# Motherboard.net
KiCad netlist of a schematic drawn in EAGLE
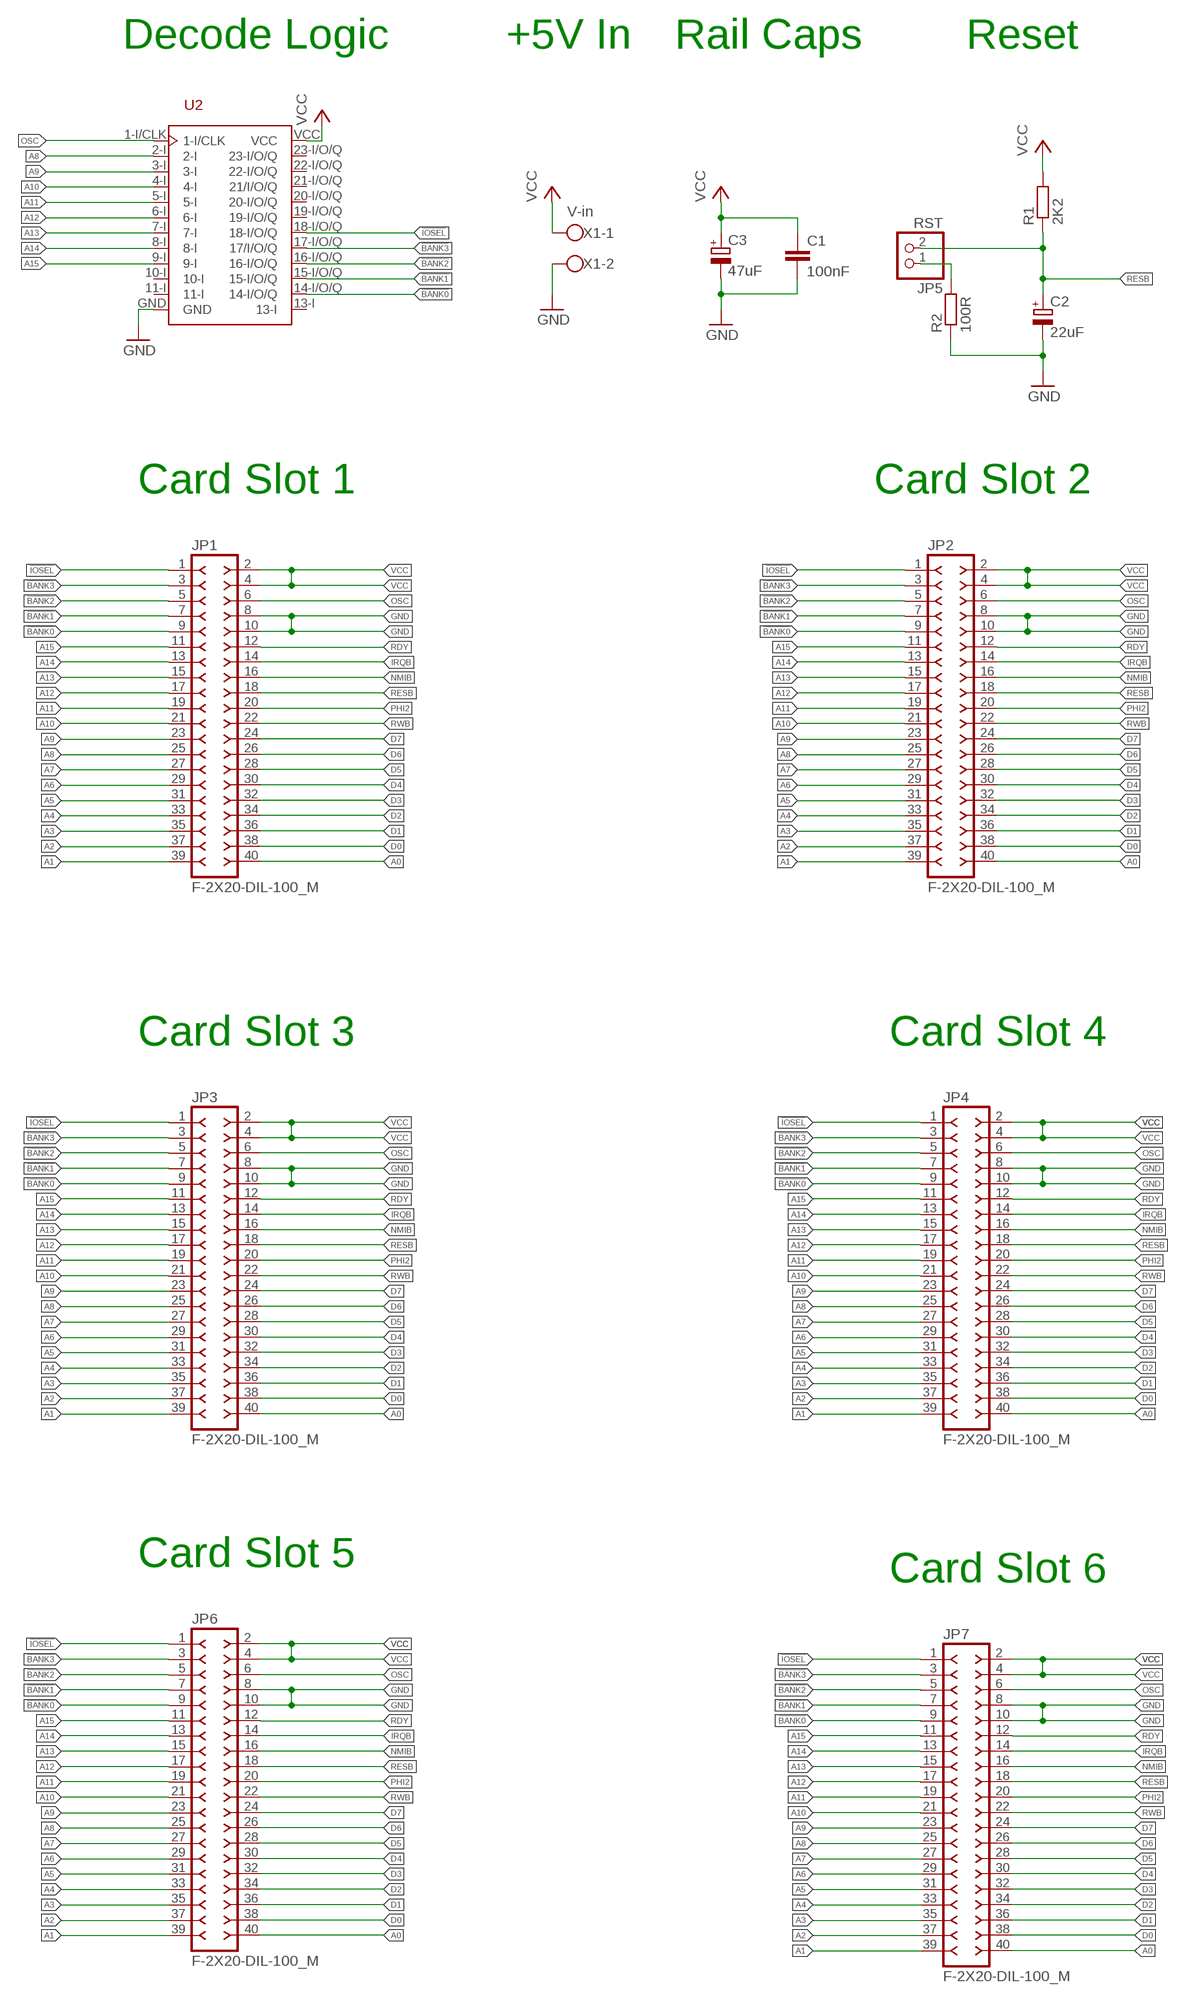
[diagram p0: schematic, sheet 1]

(export (version "E")
  (design (tool "Eeschema 10.0.6"))
  (components
    (comp (ref "C1")
      (value "100nF")
      (footprint "eagle-import:C050-025X075")
      (libsource (lib "eagle-import") (part "C-EU050-025X075"))
    )
    (comp (ref "C2")
      (value "22uF")
      (footprint "eagle-import:E2-5")
      (libsource (lib "eagle-import") (part "CPOL-EUE2-5"))
    )
    (comp (ref "C3")
      (value "47uF")
      (footprint "eagle-import:E2,5-7")
      (libsource (lib "eagle-import") (part "CPOL-EUE2.5-7"))
    )
    (comp (ref "JP1")
      (value "F-2X20-DIL-100_M")
      (footprint "eagle-import:DIL-100-2X20_M")
      (libsource (lib "eagle-import") (part "F-2X20-DIL-100_M"))
    )
    (comp (ref "JP2")
      (value "F-2X20-DIL-100_M")
      (footprint "eagle-import:DIL-100-2X20_M")
      (libsource (lib "eagle-import") (part "F-2X20-DIL-100_M"))
    )
    (comp (ref "JP3")
      (value "F-2X20-DIL-100_M")
      (footprint "eagle-import:DIL-100-2X20_M")
      (libsource (lib "eagle-import") (part "F-2X20-DIL-100_M"))
    )
    (comp (ref "JP4")
      (value "F-2X20-DIL-100_M")
      (footprint "eagle-import:DIL-100-2X20_M")
      (libsource (lib "eagle-import") (part "F-2X20-DIL-100_M"))
    )
    (comp (ref "JP5")
      (value "RST")
      (footprint "eagle-import:1X02")
      (libsource (lib "eagle-import") (part "PINHD-1X2"))
    )
    (comp (ref "JP6")
      (value "F-2X20-DIL-100_M")
      (footprint "eagle-import:DIL-100-2X20_M")
      (libsource (lib "eagle-import") (part "F-2X20-DIL-100_M"))
    )
    (comp (ref "JP7")
      (value "F-2X20-DIL-100_M")
      (footprint "eagle-import:DIL-100-2X20_M")
      (libsource (lib "eagle-import") (part "F-2X20-DIL-100_M"))
    )
    (comp (ref "R1")
      (value "2K2")
      (footprint "eagle-import:0207_10")
      (libsource (lib "eagle-import") (part "R-EU_0207/10"))
    )
    (comp (ref "R2")
      (value "100R")
      (footprint "eagle-import:0207_10")
      (libsource (lib "eagle-import") (part "R-EU_0207/10"))
    )
    (comp (ref "U2")
      (value "GAL22V10D-DIP")
      (footprint "eagle-import:DIP24")
      (libsource (lib "eagle-import") (part "GAL22V10D-DIP"))
    )
    (comp (ref "X1")
      (value "V-in")
      (footprint "eagle-import:W237-102")
      (fields (field (name "MPN") "237-102"))
      (libsource (lib "eagle-import") (part "W237-102"))
    )
  )
  (nets
    (net (code "1") (name "/~{BANK0}") (class "Default")
      (node (ref "JP1") (pin "9") (pinfunction "9_9") (pintype "passive"))
      (node (ref "JP2") (pin "9") (pinfunction "9_9") (pintype "passive"))
      (node (ref "JP3") (pin "9") (pinfunction "9_9") (pintype "passive"))
      (node (ref "JP4") (pin "9") (pinfunction "9_9") (pintype "passive"))
      (node (ref "JP6") (pin "9") (pinfunction "9_9") (pintype "passive"))
      (node (ref "JP7") (pin "9") (pinfunction "9_9") (pintype "passive"))
      (node (ref "U2") (pin "14-I/O/Q") (pinfunction "14-I/O/Q_14-I/O/Q") (pintype "bidirectional"))
    )
    (net (code "2") (name "/~{BANK1}") (class "Default")
      (node (ref "JP1") (pin "7") (pinfunction "7_7") (pintype "passive"))
      (node (ref "JP2") (pin "7") (pinfunction "7_7") (pintype "passive"))
      (node (ref "JP3") (pin "7") (pinfunction "7_7") (pintype "passive"))
      (node (ref "JP4") (pin "7") (pinfunction "7_7") (pintype "passive"))
      (node (ref "JP6") (pin "7") (pinfunction "7_7") (pintype "passive"))
      (node (ref "JP7") (pin "7") (pinfunction "7_7") (pintype "passive"))
      (node (ref "U2") (pin "15-I/O/Q") (pinfunction "15-I/O/Q_15-I/O/Q") (pintype "bidirectional"))
    )
    (net (code "3") (name "/~{BANK2}") (class "Default")
      (node (ref "JP1") (pin "5") (pinfunction "5_5") (pintype "passive"))
      (node (ref "JP2") (pin "5") (pinfunction "5_5") (pintype "passive"))
      (node (ref "JP3") (pin "5") (pinfunction "5_5") (pintype "passive"))
      (node (ref "JP4") (pin "5") (pinfunction "5_5") (pintype "passive"))
      (node (ref "JP6") (pin "5") (pinfunction "5_5") (pintype "passive"))
      (node (ref "JP7") (pin "5") (pinfunction "5_5") (pintype "passive"))
      (node (ref "U2") (pin "16-I/O/Q") (pinfunction "16-I/O/Q_16-I/O/Q") (pintype "bidirectional"))
    )
    (net (code "4") (name "/~{BANK3}") (class "Default")
      (node (ref "JP1") (pin "3") (pinfunction "3_3") (pintype "passive"))
      (node (ref "JP2") (pin "3") (pinfunction "3_3") (pintype "passive"))
      (node (ref "JP3") (pin "3") (pinfunction "3_3") (pintype "passive"))
      (node (ref "JP4") (pin "3") (pinfunction "3_3") (pintype "passive"))
      (node (ref "JP6") (pin "3") (pinfunction "3_3") (pintype "passive"))
      (node (ref "JP7") (pin "3") (pinfunction "3_3") (pintype "passive"))
      (node (ref "U2") (pin "17-I/O/Q") (pinfunction "17/I/O/Q_17-I/O/Q") (pintype "bidirectional"))
    )
    (net (code "5") (name "/~{IOSEL}") (class "Default")
      (node (ref "JP1") (pin "1") (pinfunction "1_1") (pintype "passive"))
      (node (ref "JP2") (pin "1") (pinfunction "1_1") (pintype "passive"))
      (node (ref "JP3") (pin "1") (pinfunction "1_1") (pintype "passive"))
      (node (ref "JP4") (pin "1") (pinfunction "1_1") (pintype "passive"))
      (node (ref "JP6") (pin "1") (pinfunction "1_1") (pintype "passive"))
      (node (ref "JP7") (pin "1") (pinfunction "1_1") (pintype "passive"))
      (node (ref "U2") (pin "18-I/O/Q") (pinfunction "18-I/O/Q_18-I/O/Q") (pintype "bidirectional"))
    )
    (net (code "6") (name "A0") (class "Default")
      (node (ref "JP1") (pin "40") (pinfunction "40_40") (pintype "passive"))
      (node (ref "JP2") (pin "40") (pinfunction "40_40") (pintype "passive"))
      (node (ref "JP3") (pin "40") (pinfunction "40_40") (pintype "passive"))
      (node (ref "JP4") (pin "40") (pinfunction "40_40") (pintype "passive"))
      (node (ref "JP6") (pin "40") (pinfunction "40_40") (pintype "passive"))
      (node (ref "JP7") (pin "40") (pinfunction "40_40") (pintype "passive"))
    )
    (net (code "7") (name "A1") (class "Default")
      (node (ref "JP1") (pin "39") (pinfunction "39_39") (pintype "passive"))
      (node (ref "JP2") (pin "39") (pinfunction "39_39") (pintype "passive"))
      (node (ref "JP3") (pin "39") (pinfunction "39_39") (pintype "passive"))
      (node (ref "JP4") (pin "39") (pinfunction "39_39") (pintype "passive"))
      (node (ref "JP6") (pin "39") (pinfunction "39_39") (pintype "passive"))
      (node (ref "JP7") (pin "39") (pinfunction "39_39") (pintype "passive"))
    )
    (net (code "8") (name "A2") (class "Default")
      (node (ref "JP1") (pin "37") (pinfunction "37_37") (pintype "passive"))
      (node (ref "JP2") (pin "37") (pinfunction "37_37") (pintype "passive"))
      (node (ref "JP3") (pin "37") (pinfunction "37_37") (pintype "passive"))
      (node (ref "JP4") (pin "37") (pinfunction "37_37") (pintype "passive"))
      (node (ref "JP6") (pin "37") (pinfunction "37_37") (pintype "passive"))
      (node (ref "JP7") (pin "37") (pinfunction "37_37") (pintype "passive"))
    )
    (net (code "9") (name "A3") (class "Default")
      (node (ref "JP1") (pin "35") (pinfunction "35_35") (pintype "passive"))
      (node (ref "JP2") (pin "35") (pinfunction "35_35") (pintype "passive"))
      (node (ref "JP3") (pin "35") (pinfunction "35_35") (pintype "passive"))
      (node (ref "JP4") (pin "35") (pinfunction "35_35") (pintype "passive"))
      (node (ref "JP6") (pin "35") (pinfunction "35_35") (pintype "passive"))
      (node (ref "JP7") (pin "35") (pinfunction "35_35") (pintype "passive"))
    )
    (net (code "10") (name "A4") (class "Default")
      (node (ref "JP1") (pin "33") (pinfunction "33_33") (pintype "passive"))
      (node (ref "JP2") (pin "33") (pinfunction "33_33") (pintype "passive"))
      (node (ref "JP3") (pin "33") (pinfunction "33_33") (pintype "passive"))
      (node (ref "JP4") (pin "33") (pinfunction "33_33") (pintype "passive"))
      (node (ref "JP6") (pin "33") (pinfunction "33_33") (pintype "passive"))
      (node (ref "JP7") (pin "33") (pinfunction "33_33") (pintype "passive"))
    )
    (net (code "11") (name "A5") (class "Default")
      (node (ref "JP1") (pin "31") (pinfunction "31_31") (pintype "passive"))
      (node (ref "JP2") (pin "31") (pinfunction "31_31") (pintype "passive"))
      (node (ref "JP3") (pin "31") (pinfunction "31_31") (pintype "passive"))
      (node (ref "JP4") (pin "31") (pinfunction "31_31") (pintype "passive"))
      (node (ref "JP6") (pin "31") (pinfunction "31_31") (pintype "passive"))
      (node (ref "JP7") (pin "31") (pinfunction "31_31") (pintype "passive"))
    )
    (net (code "12") (name "A6") (class "Default")
      (node (ref "JP1") (pin "29") (pinfunction "29_29") (pintype "passive"))
      (node (ref "JP2") (pin "29") (pinfunction "29_29") (pintype "passive"))
      (node (ref "JP3") (pin "29") (pinfunction "29_29") (pintype "passive"))
      (node (ref "JP4") (pin "29") (pinfunction "29_29") (pintype "passive"))
      (node (ref "JP6") (pin "29") (pinfunction "29_29") (pintype "passive"))
      (node (ref "JP7") (pin "29") (pinfunction "29_29") (pintype "passive"))
    )
    (net (code "13") (name "A7") (class "Default")
      (node (ref "JP1") (pin "27") (pinfunction "27_27") (pintype "passive"))
      (node (ref "JP2") (pin "27") (pinfunction "27_27") (pintype "passive"))
      (node (ref "JP3") (pin "27") (pinfunction "27_27") (pintype "passive"))
      (node (ref "JP4") (pin "27") (pinfunction "27_27") (pintype "passive"))
      (node (ref "JP6") (pin "27") (pinfunction "27_27") (pintype "passive"))
      (node (ref "JP7") (pin "27") (pinfunction "27_27") (pintype "passive"))
    )
    (net (code "14") (name "A8") (class "Default")
      (node (ref "JP1") (pin "25") (pinfunction "25_25") (pintype "passive"))
      (node (ref "JP2") (pin "25") (pinfunction "25_25") (pintype "passive"))
      (node (ref "JP3") (pin "25") (pinfunction "25_25") (pintype "passive"))
      (node (ref "JP4") (pin "25") (pinfunction "25_25") (pintype "passive"))
      (node (ref "JP6") (pin "25") (pinfunction "25_25") (pintype "passive"))
      (node (ref "JP7") (pin "25") (pinfunction "25_25") (pintype "passive"))
      (node (ref "U2") (pin "2-I") (pinfunction "2-I_2-I") (pintype "input"))
    )
    (net (code "15") (name "A9") (class "Default")
      (node (ref "JP1") (pin "23") (pinfunction "23_23") (pintype "passive"))
      (node (ref "JP2") (pin "23") (pinfunction "23_23") (pintype "passive"))
      (node (ref "JP3") (pin "23") (pinfunction "23_23") (pintype "passive"))
      (node (ref "JP4") (pin "23") (pinfunction "23_23") (pintype "passive"))
      (node (ref "JP6") (pin "23") (pinfunction "23_23") (pintype "passive"))
      (node (ref "JP7") (pin "23") (pinfunction "23_23") (pintype "passive"))
      (node (ref "U2") (pin "3-I") (pinfunction "3-I_3-I") (pintype "input"))
    )
    (net (code "16") (name "A10") (class "Default")
      (node (ref "JP1") (pin "21") (pinfunction "21_21") (pintype "passive"))
      (node (ref "JP2") (pin "21") (pinfunction "21_21") (pintype "passive"))
      (node (ref "JP3") (pin "21") (pinfunction "21_21") (pintype "passive"))
      (node (ref "JP4") (pin "21") (pinfunction "21_21") (pintype "passive"))
      (node (ref "JP6") (pin "21") (pinfunction "21_21") (pintype "passive"))
      (node (ref "JP7") (pin "21") (pinfunction "21_21") (pintype "passive"))
      (node (ref "U2") (pin "4-I") (pinfunction "4-I_4-I") (pintype "input"))
    )
    (net (code "17") (name "A11") (class "Default")
      (node (ref "JP1") (pin "19") (pinfunction "19_19") (pintype "passive"))
      (node (ref "JP2") (pin "19") (pinfunction "19_19") (pintype "passive"))
      (node (ref "JP3") (pin "19") (pinfunction "19_19") (pintype "passive"))
      (node (ref "JP4") (pin "19") (pinfunction "19_19") (pintype "passive"))
      (node (ref "JP6") (pin "19") (pinfunction "19_19") (pintype "passive"))
      (node (ref "JP7") (pin "19") (pinfunction "19_19") (pintype "passive"))
      (node (ref "U2") (pin "5-I") (pinfunction "5-I_5-I") (pintype "input"))
    )
    (net (code "18") (name "A12") (class "Default")
      (node (ref "JP1") (pin "17") (pinfunction "17_17") (pintype "passive"))
      (node (ref "JP2") (pin "17") (pinfunction "17_17") (pintype "passive"))
      (node (ref "JP3") (pin "17") (pinfunction "17_17") (pintype "passive"))
      (node (ref "JP4") (pin "17") (pinfunction "17_17") (pintype "passive"))
      (node (ref "JP6") (pin "17") (pinfunction "17_17") (pintype "passive"))
      (node (ref "JP7") (pin "17") (pinfunction "17_17") (pintype "passive"))
      (node (ref "U2") (pin "6-I") (pinfunction "6-I_6-I") (pintype "input"))
    )
    (net (code "19") (name "A13") (class "Default")
      (node (ref "JP1") (pin "15") (pinfunction "15_15") (pintype "passive"))
      (node (ref "JP2") (pin "15") (pinfunction "15_15") (pintype "passive"))
      (node (ref "JP3") (pin "15") (pinfunction "15_15") (pintype "passive"))
      (node (ref "JP4") (pin "15") (pinfunction "15_15") (pintype "passive"))
      (node (ref "JP6") (pin "15") (pinfunction "15_15") (pintype "passive"))
      (node (ref "JP7") (pin "15") (pinfunction "15_15") (pintype "passive"))
      (node (ref "U2") (pin "7-I") (pinfunction "7-I_7-I") (pintype "input"))
    )
    (net (code "20") (name "A14") (class "Default")
      (node (ref "JP1") (pin "13") (pinfunction "13_13") (pintype "passive"))
      (node (ref "JP2") (pin "13") (pinfunction "13_13") (pintype "passive"))
      (node (ref "JP3") (pin "13") (pinfunction "13_13") (pintype "passive"))
      (node (ref "JP4") (pin "13") (pinfunction "13_13") (pintype "passive"))
      (node (ref "JP6") (pin "13") (pinfunction "13_13") (pintype "passive"))
      (node (ref "JP7") (pin "13") (pinfunction "13_13") (pintype "passive"))
      (node (ref "U2") (pin "8-I") (pinfunction "8-I_8-I") (pintype "input"))
    )
    (net (code "21") (name "A15") (class "Default")
      (node (ref "JP1") (pin "11") (pinfunction "11_11") (pintype "passive"))
      (node (ref "JP2") (pin "11") (pinfunction "11_11") (pintype "passive"))
      (node (ref "JP3") (pin "11") (pinfunction "11_11") (pintype "passive"))
      (node (ref "JP4") (pin "11") (pinfunction "11_11") (pintype "passive"))
      (node (ref "JP6") (pin "11") (pinfunction "11_11") (pintype "passive"))
      (node (ref "JP7") (pin "11") (pinfunction "11_11") (pintype "passive"))
      (node (ref "U2") (pin "9-I") (pinfunction "9-I_9-I") (pintype "input"))
    )
    (net (code "22") (name "D0") (class "Default")
      (node (ref "JP1") (pin "38") (pinfunction "38_38") (pintype "passive"))
      (node (ref "JP2") (pin "38") (pinfunction "38_38") (pintype "passive"))
      (node (ref "JP3") (pin "38") (pinfunction "38_38") (pintype "passive"))
      (node (ref "JP4") (pin "38") (pinfunction "38_38") (pintype "passive"))
      (node (ref "JP6") (pin "38") (pinfunction "38_38") (pintype "passive"))
      (node (ref "JP7") (pin "38") (pinfunction "38_38") (pintype "passive"))
    )
    (net (code "23") (name "D1") (class "Default")
      (node (ref "JP1") (pin "36") (pinfunction "36_36") (pintype "passive"))
      (node (ref "JP2") (pin "36") (pinfunction "36_36") (pintype "passive"))
      (node (ref "JP3") (pin "36") (pinfunction "36_36") (pintype "passive"))
      (node (ref "JP4") (pin "36") (pinfunction "36_36") (pintype "passive"))
      (node (ref "JP6") (pin "36") (pinfunction "36_36") (pintype "passive"))
      (node (ref "JP7") (pin "36") (pinfunction "36_36") (pintype "passive"))
    )
    (net (code "24") (name "D2") (class "Default")
      (node (ref "JP1") (pin "34") (pinfunction "34_34") (pintype "passive"))
      (node (ref "JP2") (pin "34") (pinfunction "34_34") (pintype "passive"))
      (node (ref "JP3") (pin "34") (pinfunction "34_34") (pintype "passive"))
      (node (ref "JP4") (pin "34") (pinfunction "34_34") (pintype "passive"))
      (node (ref "JP6") (pin "34") (pinfunction "34_34") (pintype "passive"))
      (node (ref "JP7") (pin "34") (pinfunction "34_34") (pintype "passive"))
    )
    (net (code "25") (name "D3") (class "Default")
      (node (ref "JP1") (pin "32") (pinfunction "32_32") (pintype "passive"))
      (node (ref "JP2") (pin "32") (pinfunction "32_32") (pintype "passive"))
      (node (ref "JP3") (pin "32") (pinfunction "32_32") (pintype "passive"))
      (node (ref "JP4") (pin "32") (pinfunction "32_32") (pintype "passive"))
      (node (ref "JP6") (pin "32") (pinfunction "32_32") (pintype "passive"))
      (node (ref "JP7") (pin "32") (pinfunction "32_32") (pintype "passive"))
    )
    (net (code "26") (name "D4") (class "Default")
      (node (ref "JP1") (pin "30") (pinfunction "30_30") (pintype "passive"))
      (node (ref "JP2") (pin "30") (pinfunction "30_30") (pintype "passive"))
      (node (ref "JP3") (pin "30") (pinfunction "30_30") (pintype "passive"))
      (node (ref "JP4") (pin "30") (pinfunction "30_30") (pintype "passive"))
      (node (ref "JP6") (pin "30") (pinfunction "30_30") (pintype "passive"))
      (node (ref "JP7") (pin "30") (pinfunction "30_30") (pintype "passive"))
    )
    (net (code "27") (name "D5") (class "Default")
      (node (ref "JP1") (pin "28") (pinfunction "28_28") (pintype "passive"))
      (node (ref "JP2") (pin "28") (pinfunction "28_28") (pintype "passive"))
      (node (ref "JP3") (pin "28") (pinfunction "28_28") (pintype "passive"))
      (node (ref "JP4") (pin "28") (pinfunction "28_28") (pintype "passive"))
      (node (ref "JP6") (pin "28") (pinfunction "28_28") (pintype "passive"))
      (node (ref "JP7") (pin "28") (pinfunction "28_28") (pintype "passive"))
    )
    (net (code "28") (name "D6") (class "Default")
      (node (ref "JP1") (pin "26") (pinfunction "26_26") (pintype "passive"))
      (node (ref "JP2") (pin "26") (pinfunction "26_26") (pintype "passive"))
      (node (ref "JP3") (pin "26") (pinfunction "26_26") (pintype "passive"))
      (node (ref "JP4") (pin "26") (pinfunction "26_26") (pintype "passive"))
      (node (ref "JP6") (pin "26") (pinfunction "26_26") (pintype "passive"))
      (node (ref "JP7") (pin "26") (pinfunction "26_26") (pintype "passive"))
    )
    (net (code "29") (name "D7") (class "Default")
      (node (ref "JP1") (pin "24") (pinfunction "24_24") (pintype "passive"))
      (node (ref "JP2") (pin "24") (pinfunction "24_24") (pintype "passive"))
      (node (ref "JP3") (pin "24") (pinfunction "24_24") (pintype "passive"))
      (node (ref "JP4") (pin "24") (pinfunction "24_24") (pintype "passive"))
      (node (ref "JP6") (pin "24") (pinfunction "24_24") (pintype "passive"))
      (node (ref "JP7") (pin "24") (pinfunction "24_24") (pintype "passive"))
    )
    (net (code "30") (name "GND") (class "Default")
      (node (ref "C1") (pin "2") (pinfunction "2_2") (pintype "passive"))
      (node (ref "C2") (pin "-") (pinfunction "-_-") (pintype "passive"))
      (node (ref "C3") (pin "-") (pinfunction "-_-") (pintype "passive"))
      (node (ref "JP1") (pin "10") (pinfunction "10_10") (pintype "passive"))
      (node (ref "JP1") (pin "8") (pinfunction "8_8") (pintype "passive"))
      (node (ref "JP2") (pin "10") (pinfunction "10_10") (pintype "passive"))
      (node (ref "JP2") (pin "8") (pinfunction "8_8") (pintype "passive"))
      (node (ref "JP3") (pin "10") (pinfunction "10_10") (pintype "passive"))
      (node (ref "JP3") (pin "8") (pinfunction "8_8") (pintype "passive"))
      (node (ref "JP4") (pin "10") (pinfunction "10_10") (pintype "passive"))
      (node (ref "JP4") (pin "8") (pinfunction "8_8") (pintype "passive"))
      (node (ref "JP6") (pin "10") (pinfunction "10_10") (pintype "passive"))
      (node (ref "JP6") (pin "8") (pinfunction "8_8") (pintype "passive"))
      (node (ref "JP7") (pin "10") (pinfunction "10_10") (pintype "passive"))
      (node (ref "JP7") (pin "8") (pinfunction "8_8") (pintype "passive"))
      (node (ref "R2") (pin "1") (pinfunction "1_1") (pintype "passive"))
      (node (ref "U2") (pin "GND") (pinfunction "GND_GND") (pintype "power_in"))
      (node (ref "X1") (pin "2") (pinfunction "KL_2") (pintype "passive"))
    )
    (net (code "31") (name "IRQB") (class "Default")
      (node (ref "JP1") (pin "14") (pinfunction "14_14") (pintype "passive"))
      (node (ref "JP2") (pin "14") (pinfunction "14_14") (pintype "passive"))
      (node (ref "JP3") (pin "14") (pinfunction "14_14") (pintype "passive"))
      (node (ref "JP4") (pin "14") (pinfunction "14_14") (pintype "passive"))
      (node (ref "JP6") (pin "14") (pinfunction "14_14") (pintype "passive"))
      (node (ref "JP7") (pin "14") (pinfunction "14_14") (pintype "passive"))
    )
    (net (code "32") (name "NMIB") (class "Default")
      (node (ref "JP1") (pin "16") (pinfunction "16_16") (pintype "passive"))
      (node (ref "JP2") (pin "16") (pinfunction "16_16") (pintype "passive"))
      (node (ref "JP3") (pin "16") (pinfunction "16_16") (pintype "passive"))
      (node (ref "JP4") (pin "16") (pinfunction "16_16") (pintype "passive"))
      (node (ref "JP6") (pin "16") (pinfunction "16_16") (pintype "passive"))
      (node (ref "JP7") (pin "16") (pinfunction "16_16") (pintype "passive"))
    )
    (net (code "33") (name "Net-(JP5-Pad1)") (class "Default")
      (node (ref "JP5") (pin "1") (pinfunction "1_1") (pintype "passive"))
      (node (ref "R2") (pin "2") (pinfunction "2_2") (pintype "passive"))
    )
    (net (code "34") (name "OSC") (class "Default")
      (node (ref "JP1") (pin "6") (pinfunction "6_6") (pintype "passive"))
      (node (ref "JP2") (pin "6") (pinfunction "6_6") (pintype "passive"))
      (node (ref "JP3") (pin "6") (pinfunction "6_6") (pintype "passive"))
      (node (ref "JP4") (pin "6") (pinfunction "6_6") (pintype "passive"))
      (node (ref "JP6") (pin "6") (pinfunction "6_6") (pintype "passive"))
      (node (ref "JP7") (pin "6") (pinfunction "6_6") (pintype "passive"))
      (node (ref "U2") (pin "1-I/CLK") (pinfunction "1-I/CLK_1-I/CLK") (pintype "input"))
    )
    (net (code "35") (name "PHI2") (class "Default")
      (node (ref "JP1") (pin "20") (pinfunction "20_20") (pintype "passive"))
      (node (ref "JP2") (pin "20") (pinfunction "20_20") (pintype "passive"))
      (node (ref "JP3") (pin "20") (pinfunction "20_20") (pintype "passive"))
      (node (ref "JP4") (pin "20") (pinfunction "20_20") (pintype "passive"))
      (node (ref "JP6") (pin "20") (pinfunction "20_20") (pintype "passive"))
      (node (ref "JP7") (pin "20") (pinfunction "20_20") (pintype "passive"))
    )
    (net (code "36") (name "RDY") (class "Default")
      (node (ref "JP1") (pin "12") (pinfunction "12_12") (pintype "passive"))
      (node (ref "JP2") (pin "12") (pinfunction "12_12") (pintype "passive"))
      (node (ref "JP3") (pin "12") (pinfunction "12_12") (pintype "passive"))
      (node (ref "JP4") (pin "12") (pinfunction "12_12") (pintype "passive"))
      (node (ref "JP6") (pin "12") (pinfunction "12_12") (pintype "passive"))
      (node (ref "JP7") (pin "12") (pinfunction "12_12") (pintype "passive"))
    )
    (net (code "37") (name "RESB") (class "Default")
      (node (ref "C2") (pin "+") (pinfunction "+_+") (pintype "passive"))
      (node (ref "JP1") (pin "18") (pinfunction "18_18") (pintype "passive"))
      (node (ref "JP2") (pin "18") (pinfunction "18_18") (pintype "passive"))
      (node (ref "JP3") (pin "18") (pinfunction "18_18") (pintype "passive"))
      (node (ref "JP4") (pin "18") (pinfunction "18_18") (pintype "passive"))
      (node (ref "JP5") (pin "2") (pinfunction "2_2") (pintype "passive"))
      (node (ref "JP6") (pin "18") (pinfunction "18_18") (pintype "passive"))
      (node (ref "JP7") (pin "18") (pinfunction "18_18") (pintype "passive"))
      (node (ref "R1") (pin "1") (pinfunction "1_1") (pintype "passive"))
    )
    (net (code "38") (name "RWB") (class "Default")
      (node (ref "JP1") (pin "22") (pinfunction "22_22") (pintype "passive"))
      (node (ref "JP2") (pin "22") (pinfunction "22_22") (pintype "passive"))
      (node (ref "JP3") (pin "22") (pinfunction "22_22") (pintype "passive"))
      (node (ref "JP4") (pin "22") (pinfunction "22_22") (pintype "passive"))
      (node (ref "JP6") (pin "22") (pinfunction "22_22") (pintype "passive"))
      (node (ref "JP7") (pin "22") (pinfunction "22_22") (pintype "passive"))
    )
    (net (code "39") (name "VCC") (class "Default")
      (node (ref "C1") (pin "1") (pinfunction "1_1") (pintype "passive"))
      (node (ref "C3") (pin "+") (pinfunction "+_+") (pintype "passive"))
      (node (ref "JP1") (pin "2") (pinfunction "2_2") (pintype "passive"))
      (node (ref "JP1") (pin "4") (pinfunction "4_4") (pintype "passive"))
      (node (ref "JP2") (pin "2") (pinfunction "2_2") (pintype "passive"))
      (node (ref "JP2") (pin "4") (pinfunction "4_4") (pintype "passive"))
      (node (ref "JP3") (pin "2") (pinfunction "2_2") (pintype "passive"))
      (node (ref "JP3") (pin "4") (pinfunction "4_4") (pintype "passive"))
      (node (ref "JP4") (pin "2") (pinfunction "2_2") (pintype "passive"))
      (node (ref "JP4") (pin "4") (pinfunction "4_4") (pintype "passive"))
      (node (ref "JP6") (pin "2") (pinfunction "2_2") (pintype "passive"))
      (node (ref "JP6") (pin "4") (pinfunction "4_4") (pintype "passive"))
      (node (ref "JP7") (pin "2") (pinfunction "2_2") (pintype "passive"))
      (node (ref "JP7") (pin "4") (pinfunction "4_4") (pintype "passive"))
      (node (ref "R1") (pin "2") (pinfunction "2_2") (pintype "passive"))
      (node (ref "U2") (pin "VCC") (pinfunction "VCC_VCC") (pintype "power_in"))
      (node (ref "X1") (pin "1") (pinfunction "KL_1") (pintype "passive"))
    )
    (net (code "40") (name "unconnected-(U2-21{slash}I{slash}O{slash}Q-Pad21-I{slash}O{slash}Q)") (class "Default")
      (node (ref "U2") (pin "21-I/O/Q") (pinfunction "21/I/O/Q_21-I/O/Q") (pintype "bidirectional"))
    )
    (net (code "41") (name "unconnected-(U2-Pad10-I)") (class "Default")
      (node (ref "U2") (pin "10-I") (pinfunction "10-I_10-I") (pintype "input"))
    )
    (net (code "42") (name "unconnected-(U2-Pad11-I)") (class "Default")
      (node (ref "U2") (pin "11-I") (pinfunction "11-I_11-I") (pintype "input"))
    )
    (net (code "43") (name "unconnected-(U2-Pad13-I)") (class "Default")
      (node (ref "U2") (pin "13-I") (pinfunction "13-I_13-I") (pintype "input"))
    )
    (net (code "44") (name "unconnected-(U2-Pad19-I{slash}O{slash}Q)") (class "Default")
      (node (ref "U2") (pin "19-I/O/Q") (pinfunction "19-I/O/Q_19-I/O/Q") (pintype "bidirectional"))
    )
    (net (code "45") (name "unconnected-(U2-Pad20-I{slash}O{slash}Q)") (class "Default")
      (node (ref "U2") (pin "20-I/O/Q") (pinfunction "20-I/O/Q_20-I/O/Q") (pintype "bidirectional"))
    )
    (net (code "46") (name "unconnected-(U2-Pad22-I{slash}O{slash}Q)") (class "Default")
      (node (ref "U2") (pin "22-I/O/Q") (pinfunction "22-I/O/Q_22-I/O/Q") (pintype "bidirectional"))
    )
    (net (code "47") (name "unconnected-(U2-Pad23-I{slash}O{slash}Q)") (class "Default")
      (node (ref "U2") (pin "23-I/O/Q") (pinfunction "23-I/O/Q_23-I/O/Q") (pintype "bidirectional"))
    )
  )
)
